# memory.net
KiCad netlist of a schematic drawn in Altium Designer
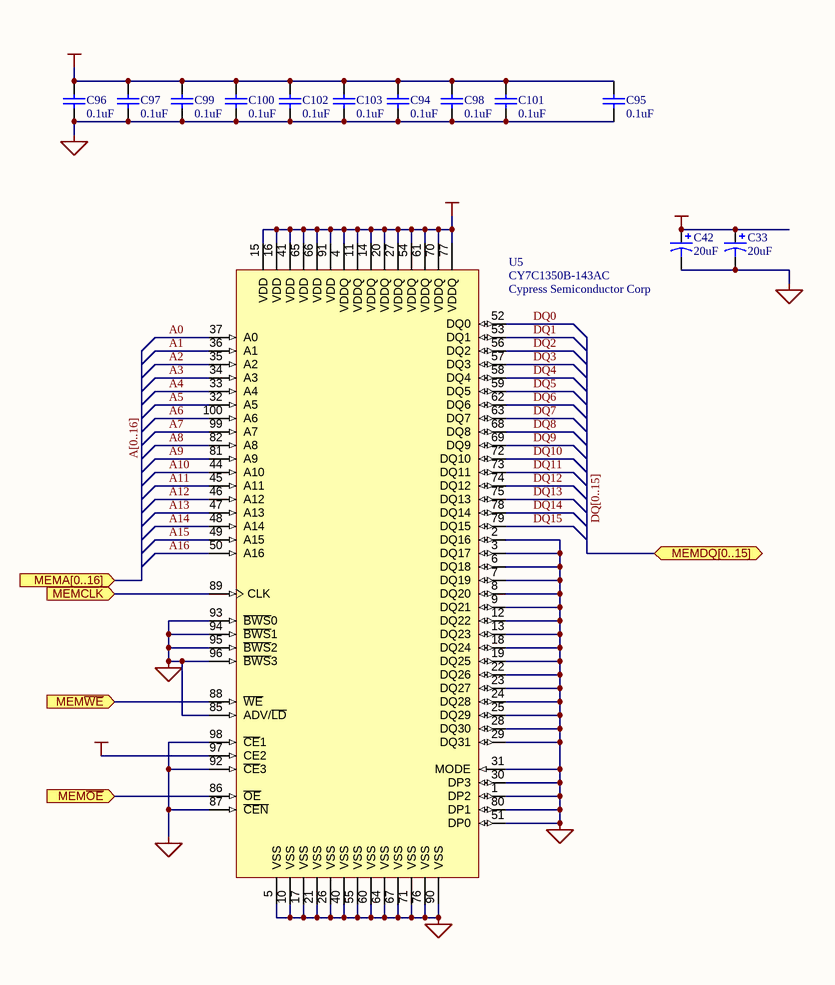
[diagram p0: memory.SCHDOC]

(export (version "E")
  (design (tool "Eeschema 10.0.6"))
  (components
    (comp (ref "C33")
      (value "20uF")
      (footprint "C")
      (description "Polarized Capacitor (Radial)")
      (fields (field (name "Comment") "Cap Pol1") (field (name "PUBLISHER") "Altium Limited"))
      (libsource (lib "Miscellaneous Devices") (part "Cap Pol1"))
    )
    (comp (ref "C42")
      (value "20uF")
      (footprint "C")
      (description "Polarized Capacitor (Radial)")
      (fields (field (name "Comment") "Cap Pol1") (field (name "PUBLISHER") "Altium Limited"))
      (libsource (lib "Miscellaneous Devices") (part "Cap Pol1"))
    )
    (comp (ref "C94")
      (value "0.1uF")
      (footprint "CC1005-0402")
      (description "Capacitor")
      (fields
        (field (name "MANUFACTURER") "Generic Components")
        (field (name "Comment") "Cap")
        (field (name "PUBLISHER") "Altium Limited")
      )
      (libsource (lib "Miscellaneous Devices") (part "Cap"))
    )
    (comp (ref "C95")
      (value "0.1uF")
      (footprint "CC1005-0402")
      (description "Capacitor")
      (fields
        (field (name "MANUFACTURER") "Generic Components")
        (field (name "Comment") "Cap")
        (field (name "PUBLISHER") "Altium Limited")
      )
      (libsource (lib "Miscellaneous Devices") (part "Cap"))
    )
    (comp (ref "C96")
      (value "0.1uF")
      (footprint "CC1005-0402")
      (description "Capacitor")
      (fields
        (field (name "MANUFACTURER") "Generic Components")
        (field (name "Comment") "Cap")
        (field (name "PUBLISHER") "Altium Limited")
      )
      (libsource (lib "Miscellaneous Devices") (part "Cap"))
    )
    (comp (ref "C97")
      (value "0.1uF")
      (footprint "CC1005-0402")
      (description "Capacitor")
      (fields
        (field (name "MANUFACTURER") "Generic Components")
        (field (name "Comment") "Cap")
        (field (name "PUBLISHER") "Altium Limited")
      )
      (libsource (lib "Miscellaneous Devices") (part "Cap"))
    )
    (comp (ref "C98")
      (value "0.1uF")
      (footprint "CC1005-0402")
      (description "Capacitor")
      (fields
        (field (name "MANUFACTURER") "Generic Components")
        (field (name "Comment") "Cap")
        (field (name "PUBLISHER") "Altium Limited")
      )
      (libsource (lib "Miscellaneous Devices") (part "Cap"))
    )
    (comp (ref "C99")
      (value "0.1uF")
      (footprint "CC1005-0402")
      (description "Capacitor")
      (fields
        (field (name "MANUFACTURER") "Generic Components")
        (field (name "Comment") "Cap")
        (field (name "PUBLISHER") "Altium Limited")
      )
      (libsource (lib "Miscellaneous Devices") (part "Cap"))
    )
    (comp (ref "C100")
      (value "0.1uF")
      (footprint "CC1005-0402")
      (description "Capacitor")
      (fields
        (field (name "MANUFACTURER") "Generic Components")
        (field (name "Comment") "Cap")
        (field (name "PUBLISHER") "Altium Limited")
      )
      (libsource (lib "Miscellaneous Devices") (part "Cap"))
    )
    (comp (ref "C101")
      (value "0.1uF")
      (footprint "CC1005-0402")
      (description "Capacitor")
      (fields
        (field (name "MANUFACTURER") "Generic Components")
        (field (name "Comment") "Cap")
        (field (name "PUBLISHER") "Altium Limited")
      )
      (libsource (lib "Miscellaneous Devices") (part "Cap"))
    )
    (comp (ref "C102")
      (value "0.1uF")
      (footprint "CC1005-0402")
      (description "Capacitor")
      (fields
        (field (name "MANUFACTURER") "Generic Components")
        (field (name "Comment") "Cap")
        (field (name "PUBLISHER") "Altium Limited")
      )
      (libsource (lib "Miscellaneous Devices") (part "Cap"))
    )
    (comp (ref "C103")
      (value "0.1uF")
      (footprint "CC1005-0402")
      (description "Capacitor")
      (fields
        (field (name "MANUFACTURER") "Generic Components")
        (field (name "Comment") "Cap")
        (field (name "PUBLISHER") "Altium Limited")
      )
      (libsource (lib "Miscellaneous Devices") (part "Cap"))
    )
    (comp (ref "U5")
      (value "CY7C1350B-143AC")
      (footprint "R-QFP14x20-G100/N")
      (description "NoBL Pipelined SRAM 128kx36")
      (fields (field (name "VENDOR") "Cypress Semiconductor Corp"))
      (libsource (lib "parts") (part "CY7C1350B"))
    )
  )
  (nets
    (net (code "1") (name "/A0") (class "Default")
      (node (ref "U5") (pin "37") (pinfunction "A0_37") (pintype "input"))
    )
    (net (code "2") (name "/A1") (class "Default")
      (node (ref "U5") (pin "36") (pinfunction "A1_36") (pintype "input"))
    )
    (net (code "3") (name "/A2") (class "Default")
      (node (ref "U5") (pin "35") (pinfunction "A2_35") (pintype "input"))
    )
    (net (code "4") (name "/A3") (class "Default")
      (node (ref "U5") (pin "34") (pinfunction "A3_34") (pintype "input"))
    )
    (net (code "5") (name "/A4") (class "Default")
      (node (ref "U5") (pin "33") (pinfunction "A4_33") (pintype "input"))
    )
    (net (code "6") (name "/A5") (class "Default")
      (node (ref "U5") (pin "32") (pinfunction "A5_32") (pintype "input"))
    )
    (net (code "7") (name "/A6") (class "Default")
      (node (ref "U5") (pin "100") (pinfunction "A6_100") (pintype "input"))
    )
    (net (code "8") (name "/A7") (class "Default")
      (node (ref "U5") (pin "99") (pinfunction "A7_99") (pintype "input"))
    )
    (net (code "9") (name "/A8") (class "Default")
      (node (ref "U5") (pin "82") (pinfunction "A8_82") (pintype "input"))
    )
    (net (code "10") (name "/A9") (class "Default")
      (node (ref "U5") (pin "81") (pinfunction "A9_81") (pintype "input"))
    )
    (net (code "11") (name "/A10") (class "Default")
      (node (ref "U5") (pin "44") (pinfunction "A10_44") (pintype "input"))
    )
    (net (code "12") (name "/A11") (class "Default")
      (node (ref "U5") (pin "45") (pinfunction "A11_45") (pintype "input"))
    )
    (net (code "13") (name "/A12") (class "Default")
      (node (ref "U5") (pin "46") (pinfunction "A12_46") (pintype "input"))
    )
    (net (code "14") (name "/A13") (class "Default")
      (node (ref "U5") (pin "47") (pinfunction "A13_47") (pintype "input"))
    )
    (net (code "15") (name "/A14") (class "Default")
      (node (ref "U5") (pin "48") (pinfunction "A14_48") (pintype "input"))
    )
    (net (code "16") (name "/A15") (class "Default")
      (node (ref "U5") (pin "49") (pinfunction "A15_49") (pintype "input"))
    )
    (net (code "17") (name "/A16") (class "Default")
      (node (ref "U5") (pin "50") (pinfunction "A16_50") (pintype "input"))
    )
    (net (code "19") (name "/DQ0") (class "Default")
      (node (ref "U5") (pin "52") (pinfunction "DQ0_52") (pintype "bidirectional"))
    )
    (net (code "20") (name "/DQ1") (class "Default")
      (node (ref "U5") (pin "53") (pinfunction "DQ1_53") (pintype "bidirectional"))
    )
    (net (code "21") (name "/DQ2") (class "Default")
      (node (ref "U5") (pin "56") (pinfunction "DQ2_56") (pintype "bidirectional"))
    )
    (net (code "22") (name "/DQ3") (class "Default")
      (node (ref "U5") (pin "57") (pinfunction "DQ3_57") (pintype "bidirectional"))
    )
    (net (code "23") (name "/DQ4") (class "Default")
      (node (ref "U5") (pin "58") (pinfunction "DQ4_58") (pintype "bidirectional"))
    )
    (net (code "24") (name "/DQ5") (class "Default")
      (node (ref "U5") (pin "59") (pinfunction "DQ5_59") (pintype "bidirectional"))
    )
    (net (code "25") (name "/DQ6") (class "Default")
      (node (ref "U5") (pin "62") (pinfunction "DQ6_62") (pintype "bidirectional"))
    )
    (net (code "26") (name "/DQ7") (class "Default")
      (node (ref "U5") (pin "63") (pinfunction "DQ7_63") (pintype "bidirectional"))
    )
    (net (code "27") (name "/DQ8") (class "Default")
      (node (ref "U5") (pin "68") (pinfunction "DQ8_68") (pintype "bidirectional"))
    )
    (net (code "28") (name "/DQ9") (class "Default")
      (node (ref "U5") (pin "69") (pinfunction "DQ9_69") (pintype "bidirectional"))
    )
    (net (code "29") (name "/DQ10") (class "Default")
      (node (ref "U5") (pin "72") (pinfunction "DQ10_72") (pintype "bidirectional"))
    )
    (net (code "30") (name "/DQ11") (class "Default")
      (node (ref "U5") (pin "73") (pinfunction "DQ11_73") (pintype "bidirectional"))
    )
    (net (code "31") (name "/DQ12") (class "Default")
      (node (ref "U5") (pin "74") (pinfunction "DQ12_74") (pintype "bidirectional"))
    )
    (net (code "32") (name "/DQ13") (class "Default")
      (node (ref "U5") (pin "75") (pinfunction "DQ13_75") (pintype "bidirectional"))
    )
    (net (code "33") (name "/DQ14") (class "Default")
      (node (ref "U5") (pin "78") (pinfunction "DQ14_78") (pintype "bidirectional"))
    )
    (net (code "34") (name "/DQ15") (class "Default")
      (node (ref "U5") (pin "79") (pinfunction "DQ15_79") (pintype "bidirectional"))
    )
    (net (code "36") (name "/MEMCLK") (class "Default")
      (node (ref "U5") (pin "89") (pinfunction "CLK_89") (pintype "input"))
    )
    (net (code "37") (name "/MEM~{OE}") (class "Default")
      (node (ref "U5") (pin "86") (pinfunction "~{OE}_86") (pintype "input"))
    )
    (net (code "38") (name "/MEM~{WE}") (class "Default")
      (node (ref "U5") (pin "88") (pinfunction "~{WE}_88") (pintype "input"))
    )
    (net (code "39") (name "GND") (class "Default")
      (node (ref "C100") (pin "1") (pinfunction "1_1") (pintype "passive"))
      (node (ref "C101") (pin "1") (pinfunction "1_1") (pintype "passive"))
      (node (ref "C102") (pin "1") (pinfunction "1_1") (pintype "passive"))
      (node (ref "C103") (pin "1") (pinfunction "1_1") (pintype "passive"))
      (node (ref "C33") (pin "2") (pinfunction "2_2") (pintype "passive"))
      (node (ref "C42") (pin "2") (pinfunction "2_2") (pintype "passive"))
      (node (ref "C94") (pin "1") (pinfunction "1_1") (pintype "passive"))
      (node (ref "C95") (pin "1") (pinfunction "1_1") (pintype "passive"))
      (node (ref "C96") (pin "1") (pinfunction "1_1") (pintype "passive"))
      (node (ref "C97") (pin "1") (pinfunction "1_1") (pintype "passive"))
      (node (ref "C98") (pin "1") (pinfunction "1_1") (pintype "passive"))
      (node (ref "C99") (pin "1") (pinfunction "1_1") (pintype "passive"))
      (node (ref "U5") (pin "1") (pinfunction "DP2_1") (pintype "bidirectional"))
      (node (ref "U5") (pin "10") (pinfunction "VSS_10") (pintype "power_in"))
      (node (ref "U5") (pin "12") (pinfunction "DQ22_12") (pintype "bidirectional"))
      (node (ref "U5") (pin "13") (pinfunction "DQ23_13") (pintype "bidirectional"))
      (node (ref "U5") (pin "17") (pinfunction "VSS_17") (pintype "power_in"))
      (node (ref "U5") (pin "18") (pinfunction "DQ24_18") (pintype "bidirectional"))
      (node (ref "U5") (pin "19") (pinfunction "DQ25_19") (pintype "bidirectional"))
      (node (ref "U5") (pin "2") (pinfunction "DQ16_2") (pintype "bidirectional"))
      (node (ref "U5") (pin "21") (pinfunction "VSS_21") (pintype "power_in"))
      (node (ref "U5") (pin "22") (pinfunction "DQ26_22") (pintype "bidirectional"))
      (node (ref "U5") (pin "23") (pinfunction "DQ27_23") (pintype "bidirectional"))
      (node (ref "U5") (pin "24") (pinfunction "DQ28_24") (pintype "bidirectional"))
      (node (ref "U5") (pin "25") (pinfunction "DQ29_25") (pintype "bidirectional"))
      (node (ref "U5") (pin "26") (pinfunction "VSS_26") (pintype "power_in"))
      (node (ref "U5") (pin "28") (pinfunction "DQ30_28") (pintype "bidirectional"))
      (node (ref "U5") (pin "29") (pinfunction "DQ31_29") (pintype "bidirectional"))
      (node (ref "U5") (pin "3") (pinfunction "DQ17_3") (pintype "bidirectional"))
      (node (ref "U5") (pin "30") (pinfunction "DP3_30") (pintype "bidirectional"))
      (node (ref "U5") (pin "31") (pinfunction "MODE_31") (pintype "input"))
      (node (ref "U5") (pin "40") (pinfunction "VSS_40") (pintype "power_in"))
      (node (ref "U5") (pin "5") (pinfunction "VSS_5") (pintype "power_in"))
      (node (ref "U5") (pin "51") (pinfunction "DP0_51") (pintype "bidirectional"))
      (node (ref "U5") (pin "55") (pinfunction "VSS_55") (pintype "power_in"))
      (node (ref "U5") (pin "6") (pinfunction "DQ18_6") (pintype "bidirectional"))
      (node (ref "U5") (pin "60") (pinfunction "VSS_60") (pintype "power_in"))
      (node (ref "U5") (pin "64") (pinfunction "VSS_64") (pintype "power_in"))
      (node (ref "U5") (pin "67") (pinfunction "VSS_67") (pintype "power_in"))
      (node (ref "U5") (pin "7") (pinfunction "DQ19_7") (pintype "bidirectional"))
      (node (ref "U5") (pin "71") (pinfunction "VSS_71") (pintype "power_in"))
      (node (ref "U5") (pin "76") (pinfunction "VSS_76") (pintype "power_in"))
      (node (ref "U5") (pin "8") (pinfunction "DQ20_8") (pintype "bidirectional"))
      (node (ref "U5") (pin "80") (pinfunction "DP1_80") (pintype "bidirectional"))
      (node (ref "U5") (pin "85") (pinfunction "ADV/~{LD}_85") (pintype "input"))
      (node (ref "U5") (pin "87") (pinfunction "~{CEN}_87") (pintype "input"))
      (node (ref "U5") (pin "9") (pinfunction "DQ21_9") (pintype "bidirectional"))
      (node (ref "U5") (pin "90") (pinfunction "VSS_90") (pintype "power_in"))
      (node (ref "U5") (pin "92") (pinfunction "~{CE}3_92") (pintype "input"))
      (node (ref "U5") (pin "93") (pinfunction "~{BWS}0_93") (pintype "input"))
      (node (ref "U5") (pin "94") (pinfunction "~{BWS}1_94") (pintype "input"))
      (node (ref "U5") (pin "95") (pinfunction "~{BWS}2_95") (pintype "input"))
      (node (ref "U5") (pin "96") (pinfunction "~{BWS}3_96") (pintype "input"))
      (node (ref "U5") (pin "98") (pinfunction "~{CE}1_98") (pintype "input"))
    )
    (net (code "40") (name "VCC") (class "Default")
      (node (ref "C100") (pin "2") (pinfunction "2_2") (pintype "passive"))
      (node (ref "C101") (pin "2") (pinfunction "2_2") (pintype "passive"))
      (node (ref "C102") (pin "2") (pinfunction "2_2") (pintype "passive"))
      (node (ref "C103") (pin "2") (pinfunction "2_2") (pintype "passive"))
      (node (ref "C33") (pin "1") (pinfunction "1_1") (pintype "passive"))
      (node (ref "C42") (pin "1") (pinfunction "1_1") (pintype "passive"))
      (node (ref "C94") (pin "2") (pinfunction "2_2") (pintype "passive"))
      (node (ref "C95") (pin "2") (pinfunction "2_2") (pintype "passive"))
      (node (ref "C96") (pin "2") (pinfunction "2_2") (pintype "passive"))
      (node (ref "C97") (pin "2") (pinfunction "2_2") (pintype "passive"))
      (node (ref "C98") (pin "2") (pinfunction "2_2") (pintype "passive"))
      (node (ref "C99") (pin "2") (pinfunction "2_2") (pintype "passive"))
      (node (ref "U5") (pin "11") (pinfunction "VDDQ_11") (pintype "power_in"))
      (node (ref "U5") (pin "14") (pinfunction "VDDQ_14") (pintype "power_in"))
      (node (ref "U5") (pin "15") (pinfunction "VDD_15") (pintype "power_in"))
      (node (ref "U5") (pin "16") (pinfunction "VDD_16") (pintype "power_in"))
      (node (ref "U5") (pin "20") (pinfunction "VDDQ_20") (pintype "power_in"))
      (node (ref "U5") (pin "27") (pinfunction "VDDQ_27") (pintype "power_in"))
      (node (ref "U5") (pin "4") (pinfunction "VDDQ_4") (pintype "power_in"))
      (node (ref "U5") (pin "41") (pinfunction "VDD_41") (pintype "power_in"))
      (node (ref "U5") (pin "54") (pinfunction "VDDQ_54") (pintype "power_in"))
      (node (ref "U5") (pin "61") (pinfunction "VDDQ_61") (pintype "power_in"))
      (node (ref "U5") (pin "65") (pinfunction "VDD_65") (pintype "power_in"))
      (node (ref "U5") (pin "66") (pinfunction "VDD_66") (pintype "power_in"))
      (node (ref "U5") (pin "70") (pinfunction "VDDQ_70") (pintype "power_in"))
      (node (ref "U5") (pin "77") (pinfunction "VDDQ_77") (pintype "power_in"))
      (node (ref "U5") (pin "91") (pinfunction "VDD_91") (pintype "power_in"))
      (node (ref "U5") (pin "97") (pinfunction "CE2_97") (pintype "input"))
    )
  )
)
